# 01-_-.net
KiCad netlist of a schematic drawn in Altium Designer
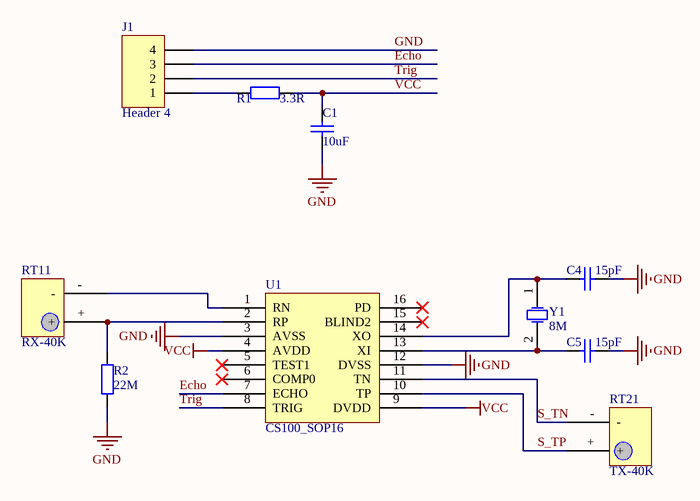
[diagram p0: 01-超声波传感器模块-原理图.SchDoc]

(export (version "E")
  (design (tool "Eeschema 10.0.6"))
  (components
    (comp (ref "C1")
      (value "10uF")
      (footprint "2012[0805]")
      (description "Capacitor")
      (fields (field (name "Comment") "Cap") (field (name "PUBLISHER") "Altium Limited"))
      (libsource (lib "Miscellaneous Devices") (part "Cap"))
    )
    (comp (ref "C4")
      (value "15pF")
      (footprint "1608[0603]")
      (description "Capacitor")
      (fields (field (name "Comment") "Cap") (field (name "PUBLISHER") "Altium Limited"))
      (libsource (lib "Miscellaneous Devices") (part "Cap"))
    )
    (comp (ref "C5")
      (value "15pF")
      (footprint "1608[0603]")
      (description "Capacitor")
      (fields (field (name "Comment") "Cap") (field (name "PUBLISHER") "Altium Limited"))
      (libsource (lib "Miscellaneous Devices") (part "Cap"))
    )
    (comp (ref "J1")
      (value "Header 4")
      (footprint "DIP4-2PCB")
      (description "Header, 4-Pin")
      (fields (field (name "PUBLISHER") "Altium Limited"))
      (libsource (lib "Miscellaneous Connectors") (part "Header 4"))
    )
    (comp (ref "R1")
      (value "3.3R")
      (footprint "1608[0603]")
      (description "Resistor")
      (fields (field (name "Comment") "Res2") (field (name "PUBLISHER") "Altium Limited"))
      (libsource (lib "Miscellaneous Devices") (part "Res2"))
    )
    (comp (ref "R2")
      (value "22M")
      (footprint "1608[0603]")
      (description "Resistor")
      (fields (field (name "Comment") "Res2") (field (name "PUBLISHER") "Altium Limited"))
      (libsource (lib "") (part "Res2_1"))
    )
    (comp (ref "RT11") (value "RX-40K") (footprint "US-16mm") (libsource (lib "USLib") (part "TC40K")))
    (comp (ref "RT21") (value "TX-40K") (footprint "US-16mm") (libsource (lib "") (part "TC40K_1")))
    (comp (ref "U1")
      (value "CS100_SOP16")
      (footprint "SOIC16")
      (libsource (lib "USLib") (part "CS100_SOP16"))
    )
    (comp (ref "Y1")
      (value "8M")
      (footprint "XTAL")
      (description "Crystal Oscillator")
      (fields (field (name "PUBLISHER") "Altium Limited"))
      (libsource (lib "Miscellaneous Devices") (part "XTAL"))
    )
  )
  (nets
    (net (code "1") (name "/Echo") (class "Default")
      (node (ref "J1") (pin "3") (pinfunction "3_3") (pintype "passive"))
      (node (ref "U1") (pin "7") (pinfunction "ECHO_7") (pintype "passive"))
    )
    (net (code "2") (name "/S_TN") (class "Default")
      (node (ref "RT21") (pin "-") (pinfunction "-_-") (pintype "passive"))
      (node (ref "U1") (pin "11") (pinfunction "TN_11") (pintype "passive"))
    )
    (net (code "3") (name "/S_TP") (class "Default")
      (node (ref "RT21") (pin "+") (pinfunction "+_+") (pintype "passive"))
      (node (ref "U1") (pin "10") (pinfunction "TP_10") (pintype "passive"))
    )
    (net (code "4") (name "/Trig") (class "Default")
      (node (ref "J1") (pin "2") (pinfunction "2_2") (pintype "passive"))
      (node (ref "U1") (pin "8") (pinfunction "TRIG_8") (pintype "passive"))
    )
    (net (code "5") (name "GND") (class "Default")
      (node (ref "C1") (pin "1") (pinfunction "1_1") (pintype "passive"))
      (node (ref "C4") (pin "2") (pinfunction "2_2") (pintype "passive"))
      (node (ref "C5") (pin "2") (pinfunction "2_2") (pintype "passive"))
      (node (ref "J1") (pin "4") (pinfunction "4_4") (pintype "passive"))
      (node (ref "R2") (pin "1") (pinfunction "1_1") (pintype "passive"))
      (node (ref "U1") (pin "12") (pinfunction "DVSS_12") (pintype "passive"))
      (node (ref "U1") (pin "3") (pinfunction "AVSS_3") (pintype "passive"))
    )
    (net (code "6") (name "Net-(J1-Pad1)") (class "Default")
      (node (ref "J1") (pin "1") (pinfunction "1_1") (pintype "passive"))
      (node (ref "R1") (pin "1") (pinfunction "1_1") (pintype "passive"))
    )
    (net (code "7") (name "Net-(U1-RN)") (class "Default")
      (node (ref "RT11") (pin "-") (pinfunction "-_-") (pintype "passive"))
      (node (ref "U1") (pin "1") (pinfunction "RN_1") (pintype "passive"))
    )
    (net (code "8") (name "Net-(U1-RP)") (class "Default")
      (node (ref "R2") (pin "2") (pinfunction "2_2") (pintype "passive"))
      (node (ref "RT11") (pin "+") (pinfunction "+_+") (pintype "passive"))
      (node (ref "U1") (pin "2") (pinfunction "RP_2") (pintype "passive"))
    )
    (net (code "9") (name "Net-(U1-XI)") (class "Default")
      (node (ref "C5") (pin "1") (pinfunction "1_1") (pintype "passive"))
      (node (ref "U1") (pin "13") (pinfunction "XI_13") (pintype "passive"))
      (node (ref "Y1") (pin "2") (pinfunction "OSC2_2") (pintype "passive"))
    )
    (net (code "10") (name "Net-(U1-XO)") (class "Default")
      (node (ref "C4") (pin "1") (pinfunction "1_1") (pintype "passive"))
      (node (ref "U1") (pin "14") (pinfunction "XO_14") (pintype "passive"))
      (node (ref "Y1") (pin "1") (pinfunction "OSC1_1") (pintype "passive"))
    )
    (net (code "11") (name "VCC") (class "Default")
      (node (ref "C1") (pin "2") (pinfunction "2_2") (pintype "passive"))
      (node (ref "R1") (pin "2") (pinfunction "2_2") (pintype "passive"))
      (node (ref "U1") (pin "4") (pinfunction "AVDD_4") (pintype "passive"))
      (node (ref "U1") (pin "9") (pinfunction "DVDD_9") (pintype "passive"))
    )
    (net (code "12") (name "unconnected-(U1-BLIND2-Pad15)") (class "Default")
      (node (ref "U1") (pin "15") (pinfunction "BLIND2_15") (pintype "passive+no_connect"))
    )
    (net (code "13") (name "unconnected-(U1-COMP0-Pad6)") (class "Default")
      (node (ref "U1") (pin "6") (pinfunction "COMP0_6") (pintype "passive+no_connect"))
    )
    (net (code "14") (name "unconnected-(U1-PD-Pad16)") (class "Default")
      (node (ref "U1") (pin "16") (pinfunction "PD_16") (pintype "passive+no_connect"))
    )
    (net (code "15") (name "unconnected-(U1-TEST1-Pad5)") (class "Default")
      (node (ref "U1") (pin "5") (pinfunction "TEST1_5") (pintype "passive+no_connect"))
    )
  )
)
